# LED_Driver_SubCkt.net
KiCad netlist of a schematic drawn in EAGLE
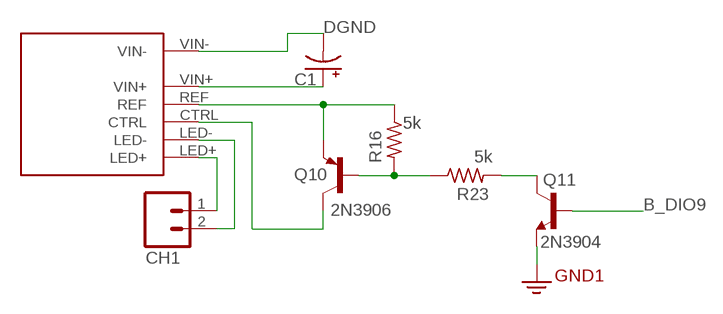
[diagram p0: schematic, sheet 1]

(export (version "E")
  (design (tool "Eeschema 10.0.6"))
  (components
    (comp (ref "BUCKPUCK1")
      (value "BUCKPUCK-350-I")
      (footprint "eagle-import:BUCKPUCK_I")
      (libsource (lib "eagle-import") (part "BUCKPUCK--?I350"))
    )
    (comp (ref "C1")
      (value "CPOL-USE5-10.5")
      (footprint "eagle-import:E5-10,5")
      (libsource (lib "eagle-import") (part "CPOL-USE5-10.5"))
    )
    (comp (ref "CH1")
      (value "M023.5MM_LOCK")
      (footprint "eagle-import:SCREWTERMINAL-3.5MM-2_LOCK")
      (libsource (lib "eagle-import") (part "M023.5MM_LOCK"))
    )
    (comp (ref "Q10")
      (value "2N3906")
      (footprint "eagle-import:SOT23-BEC")
      (libsource (lib "eagle-import") (part "-PNP-SOT23-BECMMBT3906LT1"))
    )
    (comp (ref "Q11")
      (value "2N3904")
      (footprint "eagle-import:SOT23-BEC")
      (libsource (lib "eagle-import") (part "-NPN-SOT23-BECMMBT3904LT1"))
    )
    (comp (ref "R16")
      (value "5k")
      (footprint "eagle-import:0805S")
      (libsource (lib "eagle-import") (part "RESISTOR_SM0805S"))
    )
    (comp (ref "R23")
      (value "5k")
      (footprint "eagle-import:0805S")
      (libsource (lib "eagle-import") (part "RESISTOR_SM0805S"))
    )
  )
  (nets
    (net (code "1") (name "/B_DIO9") (class "Default")
      (node (ref "Q11") (pin "B") (pinfunction "B_B") (pintype "passive"))
    )
    (net (code "2") (name "GND2") (class "Default")
      (node (ref "BUCKPUCK1") (pin "LED-") (pinfunction "LED-_LED-") (pintype "bidirectional"))
      (node (ref "BUCKPUCK1") (pin "VIN-") (pinfunction "VIN-_VIN-") (pintype "bidirectional"))
      (node (ref "C1") (pin "-") (pinfunction "-_-") (pintype "passive"))
      (node (ref "CH1") (pin "2") (pinfunction "2_2") (pintype "passive"))
      (node (ref "Q11") (pin "E") (pinfunction "E_E") (pintype "passive"))
    )
    (net (code "3") (name "Net-(BUCKPUCK1-PadCTRL)") (class "Default")
      (node (ref "BUCKPUCK1") (pin "CTRL") (pinfunction "CTRL_CTRL") (pintype "bidirectional"))
      (node (ref "Q10") (pin "C") (pinfunction "C_C") (pintype "passive"))
    )
    (net (code "4") (name "Net-(BUCKPUCK1-PadLED+)") (class "Default")
      (node (ref "BUCKPUCK1") (pin "LED+") (pinfunction "LED+_LED+") (pintype "bidirectional"))
      (node (ref "CH1") (pin "1") (pinfunction "1_1") (pintype "passive"))
    )
    (net (code "5") (name "Net-(BUCKPUCK1-PadREF)") (class "Default")
      (node (ref "BUCKPUCK1") (pin "REF") (pinfunction "REF_REF") (pintype "bidirectional"))
      (node (ref "Q10") (pin "E") (pinfunction "E_E") (pintype "passive"))
      (node (ref "R16") (pin "1") (pinfunction "1_1") (pintype "passive"))
    )
    (net (code "6") (name "Net-(BUCKPUCK1-PadVIN+)") (class "Default")
      (node (ref "BUCKPUCK1") (pin "VIN+") (pinfunction "VIN+_VIN+") (pintype "bidirectional"))
      (node (ref "C1") (pin "+") (pinfunction "+_+") (pintype "passive"))
    )
    (net (code "7") (name "Net-(Q10-PadB)") (class "Default")
      (node (ref "Q10") (pin "B") (pinfunction "B_B") (pintype "passive"))
      (node (ref "R16") (pin "2") (pinfunction "2_2") (pintype "passive"))
      (node (ref "R23") (pin "1") (pinfunction "1_1") (pintype "passive"))
    )
    (net (code "8") (name "Net-(Q11-PadC)") (class "Default")
      (node (ref "Q11") (pin "C") (pinfunction "C_C") (pintype "passive"))
      (node (ref "R23") (pin "2") (pinfunction "2_2") (pintype "passive"))
    )
  )
)
